# Power.net
KiCad netlist of a schematic drawn in Altium Designer
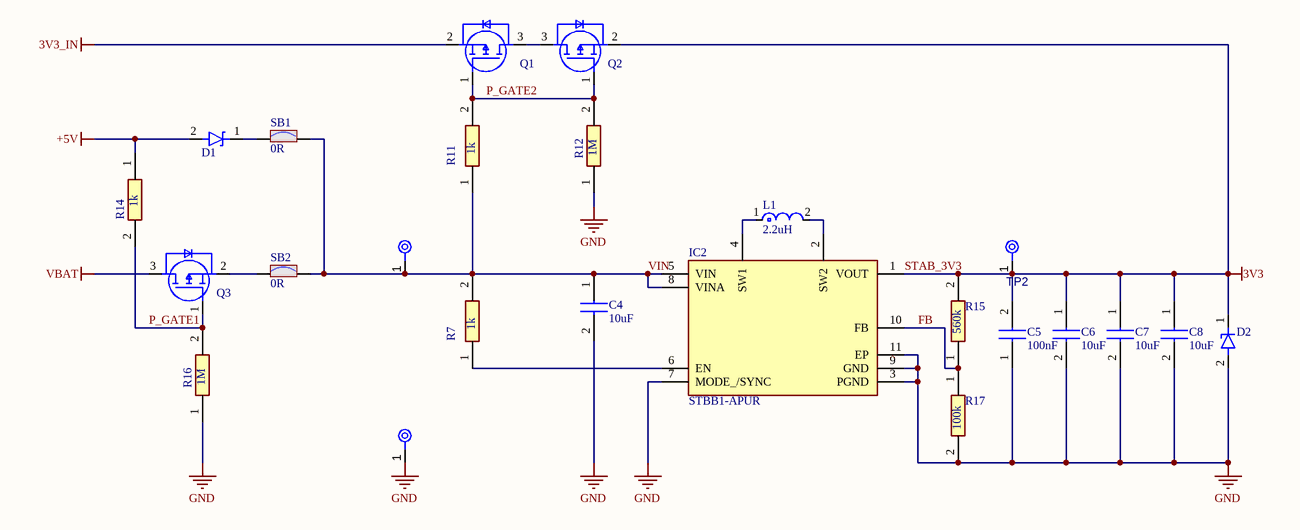
[diagram p0: Power.SchDoc]

(export (version "E")
  (design (tool "Eeschema 10.0.6"))
  (components
    (comp (ref "C4")
      (value "10uF")
      (footprint "SamacSys:GRM18x")
      (description "Capacitor")
      (fields
        (field (name "MANUFACTURER_PART_NUMBER") "GRM188R61E106KA73D")
        (field (name "MOUSER PART NUMBER") "81-GRM188R61E106KA3D")
      )
      (libsource (lib "*") (part "GRM188R61E106KA73D"))
    )
    (comp (ref "C5")
      (value "100nF")
      (footprint "SamacSys:CAPC1005X70N")
      (description "Capacitor")
      (fields
        (field (name "MANUFACTURER_PART_NUMBER") "GRM155R61A104KA01D")
        (field (name "MOUSER PART NUMBER") "81-GRM155R61A104KA01")
      )
      (libsource (lib "*") (part "GRM155R61A104KA01D"))
    )
    (comp (ref "C6")
      (value "10uF")
      (footprint "SamacSys:GRM18x")
      (description "Capacitor")
      (fields
        (field (name "MANUFACTURER_PART_NUMBER") "GRM188R61E106KA73D")
        (field (name "MOUSER PART NUMBER") "81-GRM188R61E106KA3D")
      )
      (libsource (lib "*") (part "GRM188R61E106KA73D"))
    )
    (comp (ref "C7")
      (value "10uF")
      (footprint "SamacSys:GRM18x")
      (description "Capacitor")
      (fields
        (field (name "MANUFACTURER_PART_NUMBER") "GRM188R61E106KA73D")
        (field (name "MOUSER PART NUMBER") "81-GRM188R61E106KA3D")
      )
      (libsource (lib "*") (part "GRM188R61E106KA73D"))
    )
    (comp (ref "C8")
      (value "10uF")
      (footprint "SamacSys:GRM18x")
      (description "Capacitor")
      (fields
        (field (name "MANUFACTURER_PART_NUMBER") "GRM188R61E106KA73D")
        (field (name "MOUSER PART NUMBER") "81-GRM188R61E106KA3D")
      )
      (libsource (lib "*") (part "GRM188R61E106KA73D"))
    )
    (comp (ref "D1")
      (value "RB168MM-40TFTR")
      (footprint "SamacSys:RB168MM40TFTR")
      (description "Schottky Diode")
      (fields (field (name "MOUSER PART NUMBER") "755-RB168MM-40TFTR"))
      (libsource (lib "SamacSys") (part "RB168MM-40TFTR"))
    )
    (comp (ref "D2")
      (value "SP3205-01ETG")
      (footprint "SamacSys:SP320501ETG")
      (description "Diode ESD (Uni-directional)")
      (fields (field (name "MOUSER PART NUMBER") "576-SP3205-01ETG"))
      (libsource (lib "SamacSys") (part "SP3205-01ETG"))
    )
    (comp (ref "IC2")
      (value "STBB1-APUR")
      (footprint "SamacSys:SON50P300X300X100-11N-D")
      (description "Integrated Circuit")
      (fields (field (name "MOUSER PART NUMBER") "511-STBB1-APUR"))
      (libsource (lib "SamacSys") (part "STBB1-APUR"))
    )
    (comp (ref "L1")
      (value "2.2uH")
      (footprint "FP-XFL4020-MFG")
      (description "INDUCTOR, 2.2UH, 8A, 20%, 38MHZ, REEL")
      (fields (field (name "TOLERANCE") "20%"))
      (libsource (lib "Altium Content Vault") (part "4cc4b267dca4c8e51f7102f422741d8"))
    )
    (comp (ref "Q1")
      (value "SSM3J358R,LF")
      (footprint "SamacSys:SOTFL95P240X88-3N")
      (description "MOSFET (P-Channel)")
      (fields (field (name "MOUSER PART NUMBER") "757-SSM3J358RLF"))
      (libsource (lib "SamacSys") (part "SSM3J358R,LF"))
    )
    (comp (ref "Q2")
      (value "SSM3J358R,LF")
      (footprint "SamacSys:SOTFL95P240X88-3N")
      (description "MOSFET (P-Channel)")
      (fields (field (name "MOUSER PART NUMBER") "757-SSM3J358RLF"))
      (libsource (lib "SamacSys") (part "SSM3J358R,LF"))
    )
    (comp (ref "Q3")
      (value "SSM3J358R,LF")
      (footprint "SamacSys:SOTFL95P240X88-3N")
      (description "MOSFET (P-Channel)")
      (fields (field (name "MOUSER PART NUMBER") "757-SSM3J358RLF"))
      (libsource (lib "SamacSys") (part "SSM3J358R,LF"))
    )
    (comp (ref "R7")
      (value "1k")
      (footprint "SamacSys:RESC1005X35N")
      (description "Resistor")
      (fields
        (field (name "MANUFACTURER_PART_NUMBER") "RT0402FRE071KL")
        (field (name "ARROW PART NUMBER") "RT0402FRE07100KL")
      )
      (libsource (lib "SamacSys") (part "RT0402FRE071KL"))
    )
    (comp (ref "R11")
      (value "1k")
      (footprint "SamacSys:RESC1005X35N")
      (description "Resistor")
      (fields
        (field (name "MANUFACTURER_PART_NUMBER") "RT0402FRE071KL")
        (field (name "ARROW PART NUMBER") "RT0402FRE07100KL")
      )
      (libsource (lib "SamacSys") (part "RT0402FRE071KL"))
    )
    (comp (ref "R12")
      (value "1M")
      (footprint "SamacSys:RESC1005X40N")
      (description "Resistor")
      (fields
        (field (name "MANUFACTURER_PART_NUMBER") "RC0402FR-071ML")
        (field (name "MOUSER PART NUMBER") "603-RC0402FR-071ML")
      )
      (libsource (lib "*") (part "RC0402FR-071ML"))
    )
    (comp (ref "R14")
      (value "1k")
      (footprint "SamacSys:RESC1005X35N")
      (description "Resistor")
      (fields
        (field (name "MANUFACTURER_PART_NUMBER") "RT0402FRE071KL")
        (field (name "ARROW PART NUMBER") "RT0402FRE07100KL")
      )
      (libsource (lib "") (part "RT0402FRE071KL_1"))
    )
    (comp (ref "R15")
      (value "560k")
      (footprint "SamacSys:RESC1005X40N")
      (description "Resistor")
      (fields (field (name "MANUFACTURER_PART_NUMBER") "RE0402BRE07560KL"))
      (libsource (lib "SamacSys") (part "RE0402BRE07560KL"))
    )
    (comp (ref "R16")
      (value "1M")
      (footprint "SamacSys:RESC1005X40N")
      (description "Resistor")
      (fields
        (field (name "MANUFACTURER_PART_NUMBER") "RC0402FR-071ML")
        (field (name "MOUSER PART NUMBER") "603-RC0402FR-071ML")
      )
      (libsource (lib "*") (part "RC0402FR-071ML"))
    )
    (comp (ref "R17")
      (value "100k")
      (footprint "SamacSys:RESC1005X40N")
      (description "Resistor")
      (fields (field (name "MANUFACTURER_PART_NUMBER") "RC0402BR-07100KL"))
      (libsource (lib "SamacSys") (part "RC0402BR-07100KL"))
    )
    (comp (ref "SB1")
      (value "0R")
      (footprint "SOLDER-BRIDGE_R0603-0R")
      (description "Resistor, 0R, SB0603, 5%, 0.1W")
      (fields
        (field (name "INTERNAL_PART_NUMBER") "MCD-00071")
        (field (name "MANUFACTURER_PART_NUMBER") "RC0603JR-070RL")
      )
      (libsource (lib "Copy of MB1933") (part "MCD-00071"))
    )
    (comp (ref "SB2")
      (value "0R")
      (footprint "SOLDER-BRIDGE_R0603-0R")
      (description "Resistor, 0R, SB0603, 5%, 0.1W")
      (fields
        (field (name "INTERNAL_PART_NUMBER") "MCD-00071")
        (field (name "MANUFACTURER_PART_NUMBER") "RC0603JR-070RL")
      )
      (libsource (lib "Copy of MB1933") (part "MCD-00071"))
    )
    (comp (ref "TP1")
      (value "TPAD6R")
      (footprint "TP06R")
      (description "0.6mm round")
      (libsource (lib "Západočeská Univerzita V Plzni") (part "CMP-001-0001-4"))
    )
    (comp (ref "TP2")
      (value "TPAD6R")
      (footprint "TP06R")
      (description "0.6mm round")
      (libsource (lib "Západočeská Univerzita V Plzni") (part "CMP-001-0001-4"))
    )
    (comp (ref "TP3")
      (value "TPAD6R")
      (footprint "TP06R")
      (description "0.6mm round")
      (libsource (lib "Západočeská Univerzita V Plzni") (part "CMP-001-0001-4"))
    )
  )
  (nets
    (net (code "1") (name "+5V") (class "Default")
      (node (ref "D1") (pin "2") (pinfunction "A_2") (pintype "passive"))
      (node (ref "R14") (pin "1") (pinfunction "1_1") (pintype "passive"))
    )
    (net (code "2") (name "/FB") (class "Default")
      (node (ref "IC2") (pin "10") (pinfunction "FB_10") (pintype "passive"))
      (node (ref "R15") (pin "1") (pinfunction "1_1") (pintype "passive"))
      (node (ref "R17") (pin "1") (pinfunction "1_1") (pintype "passive"))
    )
    (net (code "3") (name "/P_GATE1") (class "Default")
      (node (ref "Q3") (pin "1") (pinfunction "G_1") (pintype "passive"))
      (node (ref "R14") (pin "2") (pinfunction "2_2") (pintype "passive"))
      (node (ref "R16") (pin "2") (pinfunction "2_2") (pintype "passive"))
    )
    (net (code "4") (name "/P_GATE2") (class "Default")
      (node (ref "Q1") (pin "1") (pinfunction "G_1") (pintype "passive"))
      (node (ref "Q2") (pin "1") (pinfunction "G_1") (pintype "passive"))
      (node (ref "R11") (pin "2") (pinfunction "2_2") (pintype "passive"))
      (node (ref "R12") (pin "2") (pinfunction "2_2") (pintype "passive"))
    )
    (net (code "5") (name "/VIN") (class "Default")
      (node (ref "C4") (pin "1") (pinfunction "1_1") (pintype "passive"))
      (node (ref "IC2") (pin "5") (pinfunction "VIN_5") (pintype "passive"))
      (node (ref "IC2") (pin "8") (pinfunction "VINA_8") (pintype "passive"))
      (node (ref "R11") (pin "1") (pinfunction "1_1") (pintype "passive"))
      (node (ref "R7") (pin "2") (pinfunction "2_2") (pintype "passive"))
      (node (ref "SB1") (pin "2") (pinfunction "2_2") (pintype "passive"))
      (node (ref "SB2") (pin "2") (pinfunction "2_2") (pintype "passive"))
      (node (ref "TP1") (pin "1") (pinfunction "TP_1") (pintype "passive"))
    )
    (net (code "6") (name "3V3") (class "Default")
      (node (ref "C5") (pin "2") (pinfunction "2_2") (pintype "passive"))
      (node (ref "C6") (pin "1") (pinfunction "1_1") (pintype "passive"))
      (node (ref "C7") (pin "1") (pinfunction "1_1") (pintype "passive"))
      (node (ref "C8") (pin "1") (pinfunction "1_1") (pintype "passive"))
      (node (ref "D2") (pin "1") (pinfunction "K_1") (pintype "passive"))
      (node (ref "IC2") (pin "1") (pinfunction "VOUT_1") (pintype "passive"))
      (node (ref "Q2") (pin "2") (pinfunction "S_2") (pintype "passive"))
      (node (ref "R15") (pin "2") (pinfunction "2_2") (pintype "passive"))
      (node (ref "TP2") (pin "1") (pinfunction "TP_1") (pintype "passive"))
    )
    (net (code "7") (name "3V3_IN") (class "Default")
      (node (ref "Q1") (pin "2") (pinfunction "S_2") (pintype "passive"))
    )
    (net (code "8") (name "GND") (class "Default")
      (node (ref "C4") (pin "2") (pinfunction "2_2") (pintype "passive"))
      (node (ref "C5") (pin "1") (pinfunction "1_1") (pintype "passive"))
      (node (ref "C6") (pin "2") (pinfunction "2_2") (pintype "passive"))
      (node (ref "C7") (pin "2") (pinfunction "2_2") (pintype "passive"))
      (node (ref "C8") (pin "2") (pinfunction "2_2") (pintype "passive"))
      (node (ref "D2") (pin "2") (pinfunction "A_2") (pintype "passive"))
      (node (ref "IC2") (pin "11") (pinfunction "EP_11") (pintype "passive"))
      (node (ref "IC2") (pin "3") (pinfunction "PGND_3") (pintype "passive"))
      (node (ref "IC2") (pin "7") (pinfunction "MODE_/SYNC_7") (pintype "passive"))
      (node (ref "IC2") (pin "9") (pinfunction "GND_9") (pintype "passive"))
      (node (ref "R12") (pin "1") (pinfunction "1_1") (pintype "passive"))
      (node (ref "R16") (pin "1") (pinfunction "1_1") (pintype "passive"))
      (node (ref "R17") (pin "2") (pinfunction "2_2") (pintype "passive"))
      (node (ref "TP3") (pin "1") (pinfunction "TP_1") (pintype "passive"))
    )
    (net (code "9") (name "Net-(D1-K)") (class "Default")
      (node (ref "D1") (pin "1") (pinfunction "K_1") (pintype "passive"))
      (node (ref "SB1") (pin "1") (pinfunction "1_1") (pintype "passive"))
    )
    (net (code "10") (name "Net-(IC2-EN)") (class "Default")
      (node (ref "IC2") (pin "6") (pinfunction "EN_6") (pintype "passive"))
      (node (ref "R7") (pin "1") (pinfunction "1_1") (pintype "passive"))
    )
    (net (code "11") (name "Net-(IC2-SW1)") (class "Default")
      (node (ref "IC2") (pin "4") (pinfunction "SW1_4") (pintype "passive"))
      (node (ref "L1") (pin "1") (pinfunction "1_1") (pintype "passive"))
    )
    (net (code "12") (name "Net-(IC2-SW2)") (class "Default")
      (node (ref "IC2") (pin "2") (pinfunction "SW2_2") (pintype "passive"))
      (node (ref "L1") (pin "2") (pinfunction "2_2") (pintype "passive"))
    )
    (net (code "13") (name "Net-(Q1-D)") (class "Default")
      (node (ref "Q1") (pin "3") (pinfunction "D_3") (pintype "passive"))
      (node (ref "Q2") (pin "3") (pinfunction "D_3") (pintype "passive"))
    )
    (net (code "14") (name "Net-(Q3-S)") (class "Default")
      (node (ref "Q3") (pin "2") (pinfunction "S_2") (pintype "passive"))
      (node (ref "SB2") (pin "1") (pinfunction "1_1") (pintype "passive"))
    )
    (net (code "15") (name "VBAT") (class "Default")
      (node (ref "Q3") (pin "3") (pinfunction "D_3") (pintype "passive"))
    )
  )
)
